# LcsNodes-Diagnostic-Board-B_00_01.net
KiCad netlist of a schematic drawn in EasyEDA
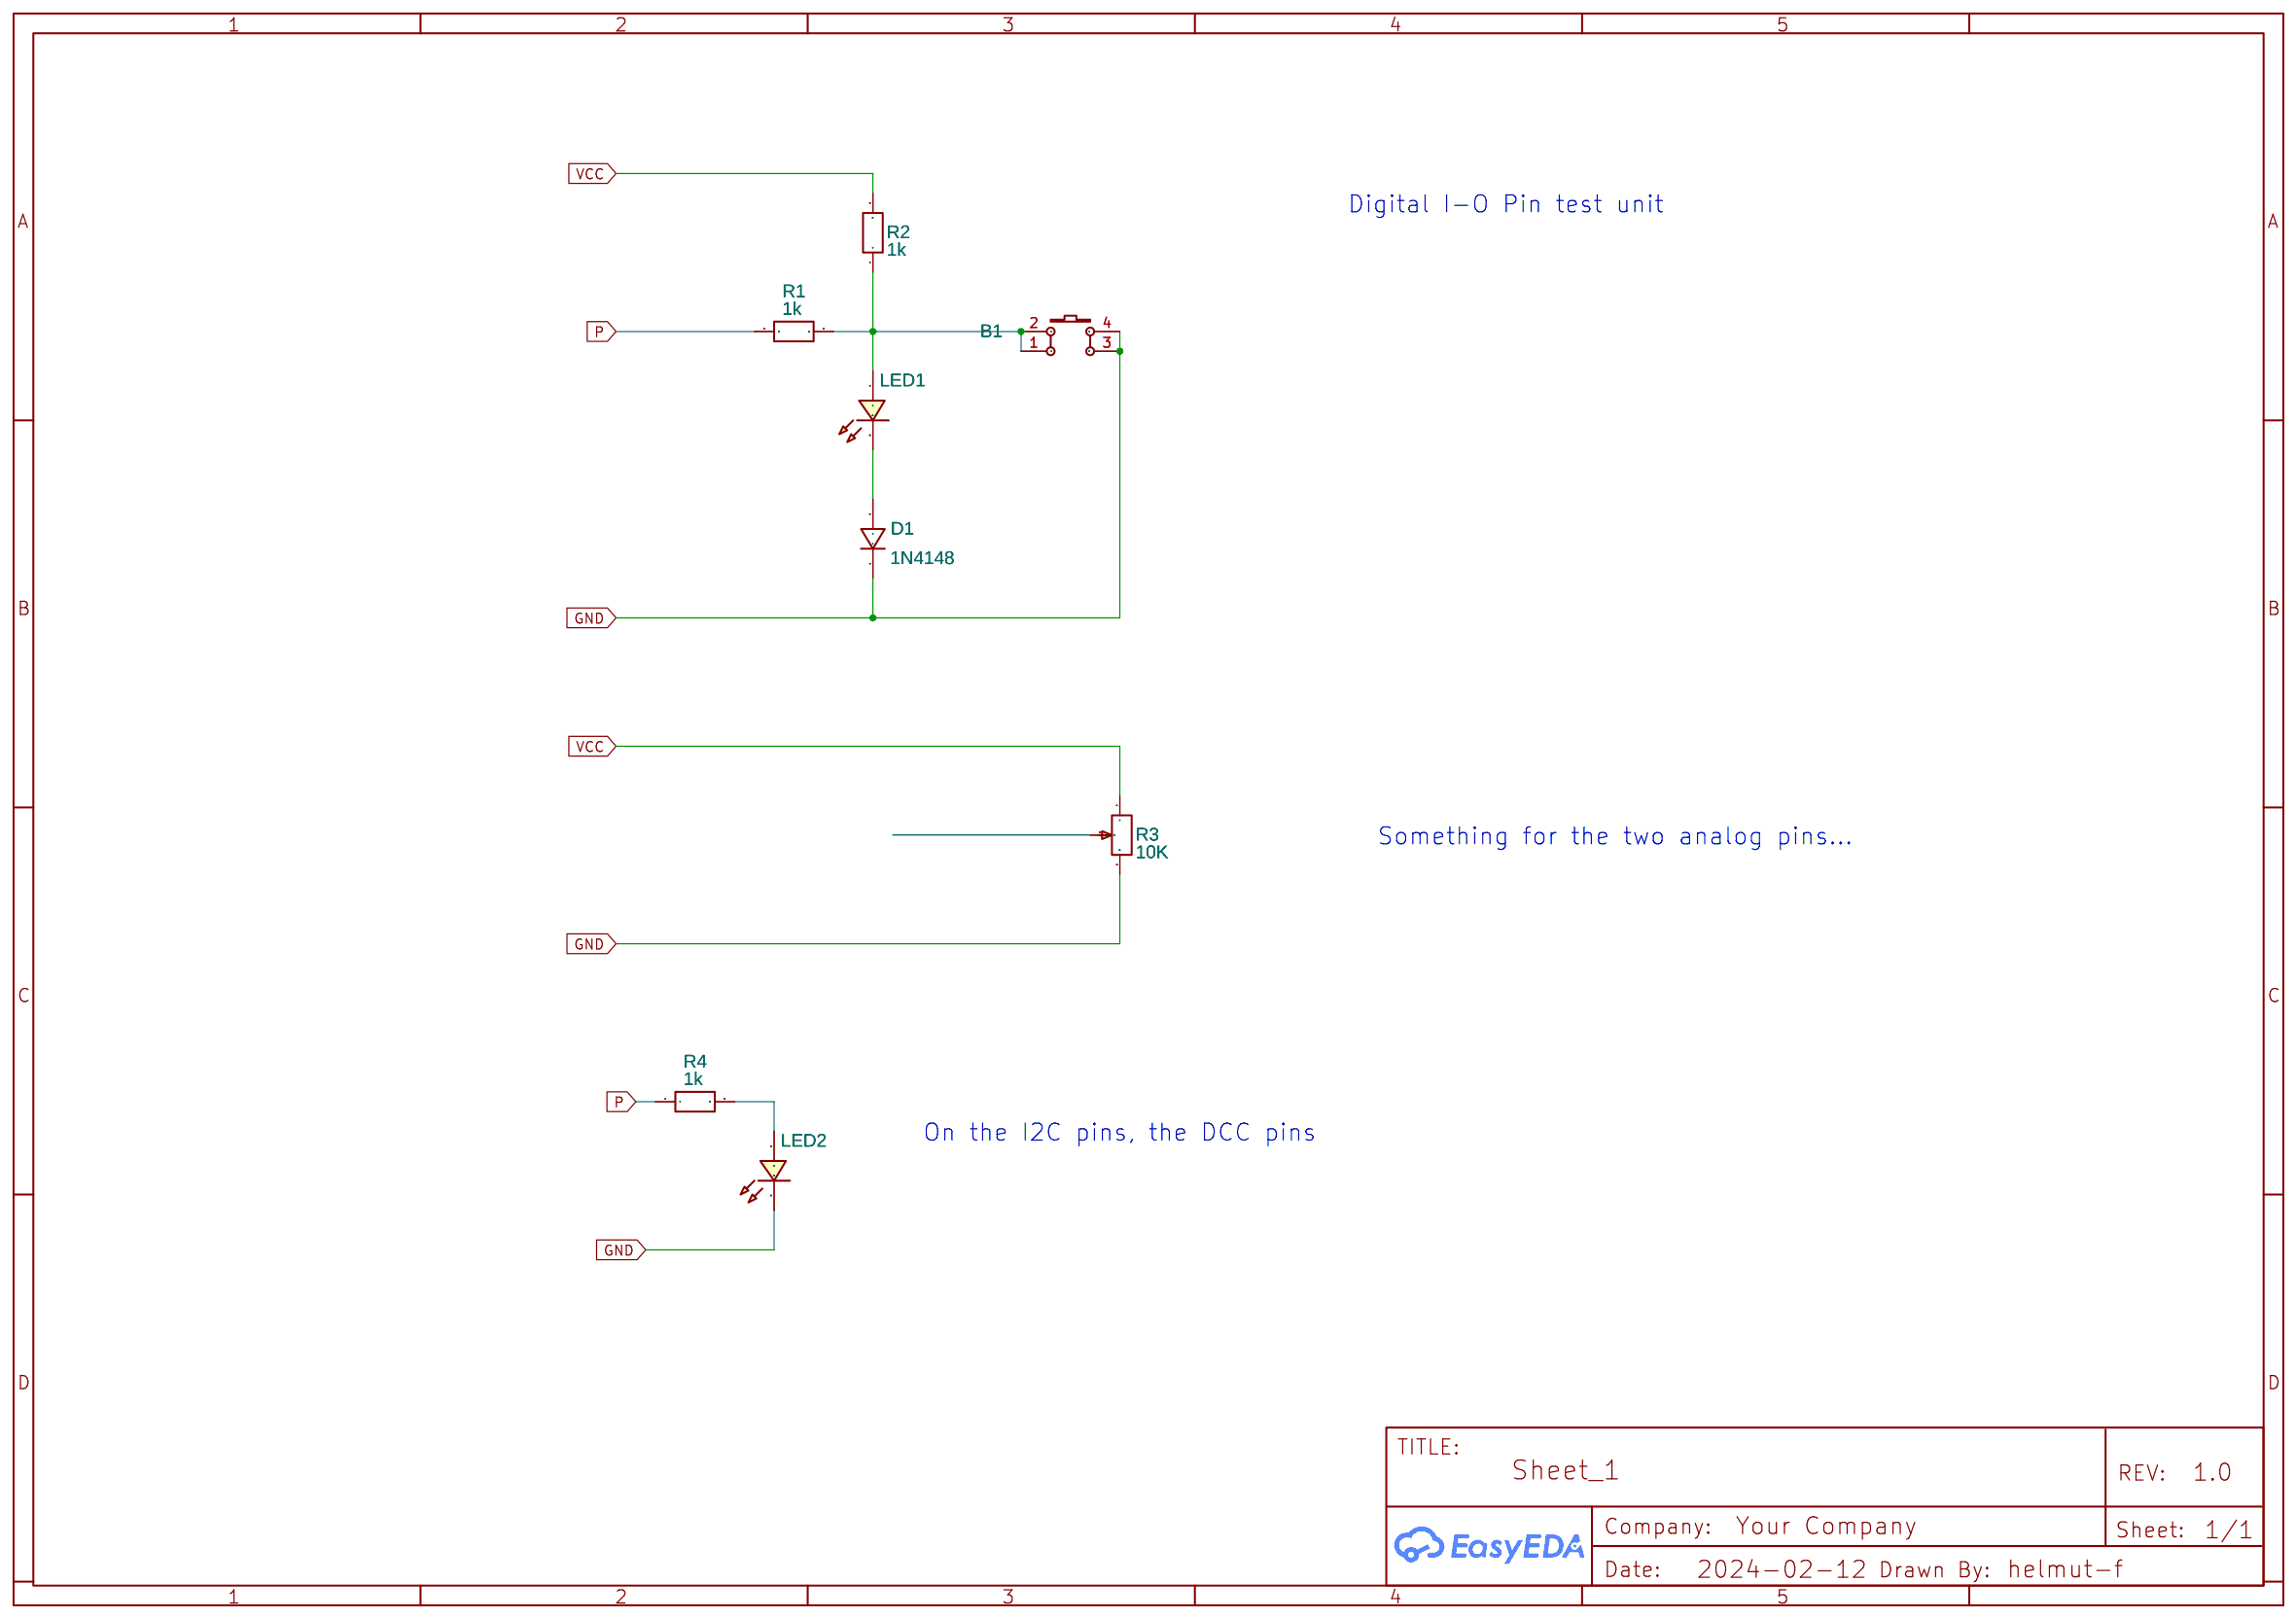
[diagram p0: schematic sheet]

(export (version "E")
  (design (tool "Eeschema 10.0.6"))
  (components
    (comp (ref "B1")
      (value "Opt")
      (fields (field (name "Manufacturer Part") "K2-1102DP-E4SW-04") (field (name "Manufacturer") "韩国韩荣"))
      (libsource (lib "") (part "K4-6×6_TH"))
    )
    (comp (ref "D1")
      (value "1N4148")
      (fields (field (name "Manufacturer") "SEMTECH"))
      (libsource (lib "") (part "1N4148"))
    )
    (comp (ref "LED1")
      (value "LED-0603_R")
      (fields
        (field (name "Manufacturer Part") "19-217/R6C-AL1M2VY/3T")
        (field (name "Manufacturer") "EVERLIGHT(台湾亿光)")
      )
      (libsource (lib "") (part "LED-0603_R"))
    )
    (comp (ref "LED2")
      (value "LED-0603_R")
      (fields
        (field (name "Manufacturer Part") "19-217/R6C-AL1M2VY/3T")
        (field (name "Manufacturer") "EVERLIGHT(台湾亿光)")
      )
      (libsource (lib "") (part "LED-0603_R"))
    )
    (comp (ref "R1") (value "1k") (libsource (lib "") (part "R_1206_EU_1")))
    (comp (ref "R2") (value "1k") (libsource (lib "") (part "R_1206_EU")))
    (comp (ref "R3")
      (value "10K")
      (fields
        (field (name "Manufacturer Part") "Precision potentiometer 3296W/50ohm")
        (field (name "Manufacturer") "ReliaPro")
      )
      (libsource (lib "") (part "Precision potentiometer 3296W/50ohm"))
    )
    (comp (ref "R4") (value "1k") (libsource (lib "") (part "R_1206_EU_1")))
  )
  (nets
    (net (code "1") (name "GND") (class "Default")
      (node (ref "B1") (pin "3") (pinfunction "3_3") (pintype "unspecified"))
      (node (ref "B1") (pin "4") (pinfunction "4_4") (pintype "unspecified"))
      (node (ref "D1") (pin "1") (pinfunction "2_1") (pintype "unspecified"))
      (node (ref "LED2") (pin "2") (pinfunction "2_2") (pintype "unspecified"))
      (node (ref "R3") (pin "3") (pinfunction "3_3") (pintype "input"))
    )
    (net (code "2") (name "Net-(B1-Pad1)") (class "Default")
      (node (ref "B1") (pin "1") (pinfunction "1_1") (pintype "unspecified"))
      (node (ref "B1") (pin "2") (pinfunction "2_2") (pintype "unspecified"))
      (node (ref "LED1") (pin "1") (pinfunction "1_1") (pintype "unspecified"))
      (node (ref "R1") (pin "2") (pinfunction "2_2") (pintype "unspecified"))
      (node (ref "R2") (pin "1") (pinfunction "1_1") (pintype "unspecified"))
    )
    (net (code "3") (name "Net-(D1-1)") (class "Default")
      (node (ref "D1") (pin "2") (pinfunction "1_2") (pintype "unspecified"))
      (node (ref "LED1") (pin "2") (pinfunction "2_2") (pintype "unspecified"))
    )
    (net (code "4") (name "Net-(LED2-Pad1)") (class "Default")
      (node (ref "LED2") (pin "1") (pinfunction "1_1") (pintype "unspecified"))
      (node (ref "R4") (pin "2") (pinfunction "2_2") (pintype "unspecified"))
    )
    (net (code "5") (name "P") (class "Default")
      (node (ref "R1") (pin "1") (pinfunction "1_1") (pintype "unspecified"))
      (node (ref "R4") (pin "1") (pinfunction "1_1") (pintype "unspecified"))
    )
    (net (code "6") (name "VCC") (class "Default")
      (node (ref "R2") (pin "2") (pinfunction "2_2") (pintype "unspecified"))
      (node (ref "R3") (pin "1") (pinfunction "1_1") (pintype "input"))
    )
    (net (code "7") (name "unconnected-(R3-Pad2)") (class "Default")
      (node (ref "R3") (pin "2") (pinfunction "2_2") (pintype "input"))
    )
  )
)
